# RapideUSB.net
KiCad netlist of a schematic drawn in EAGLE
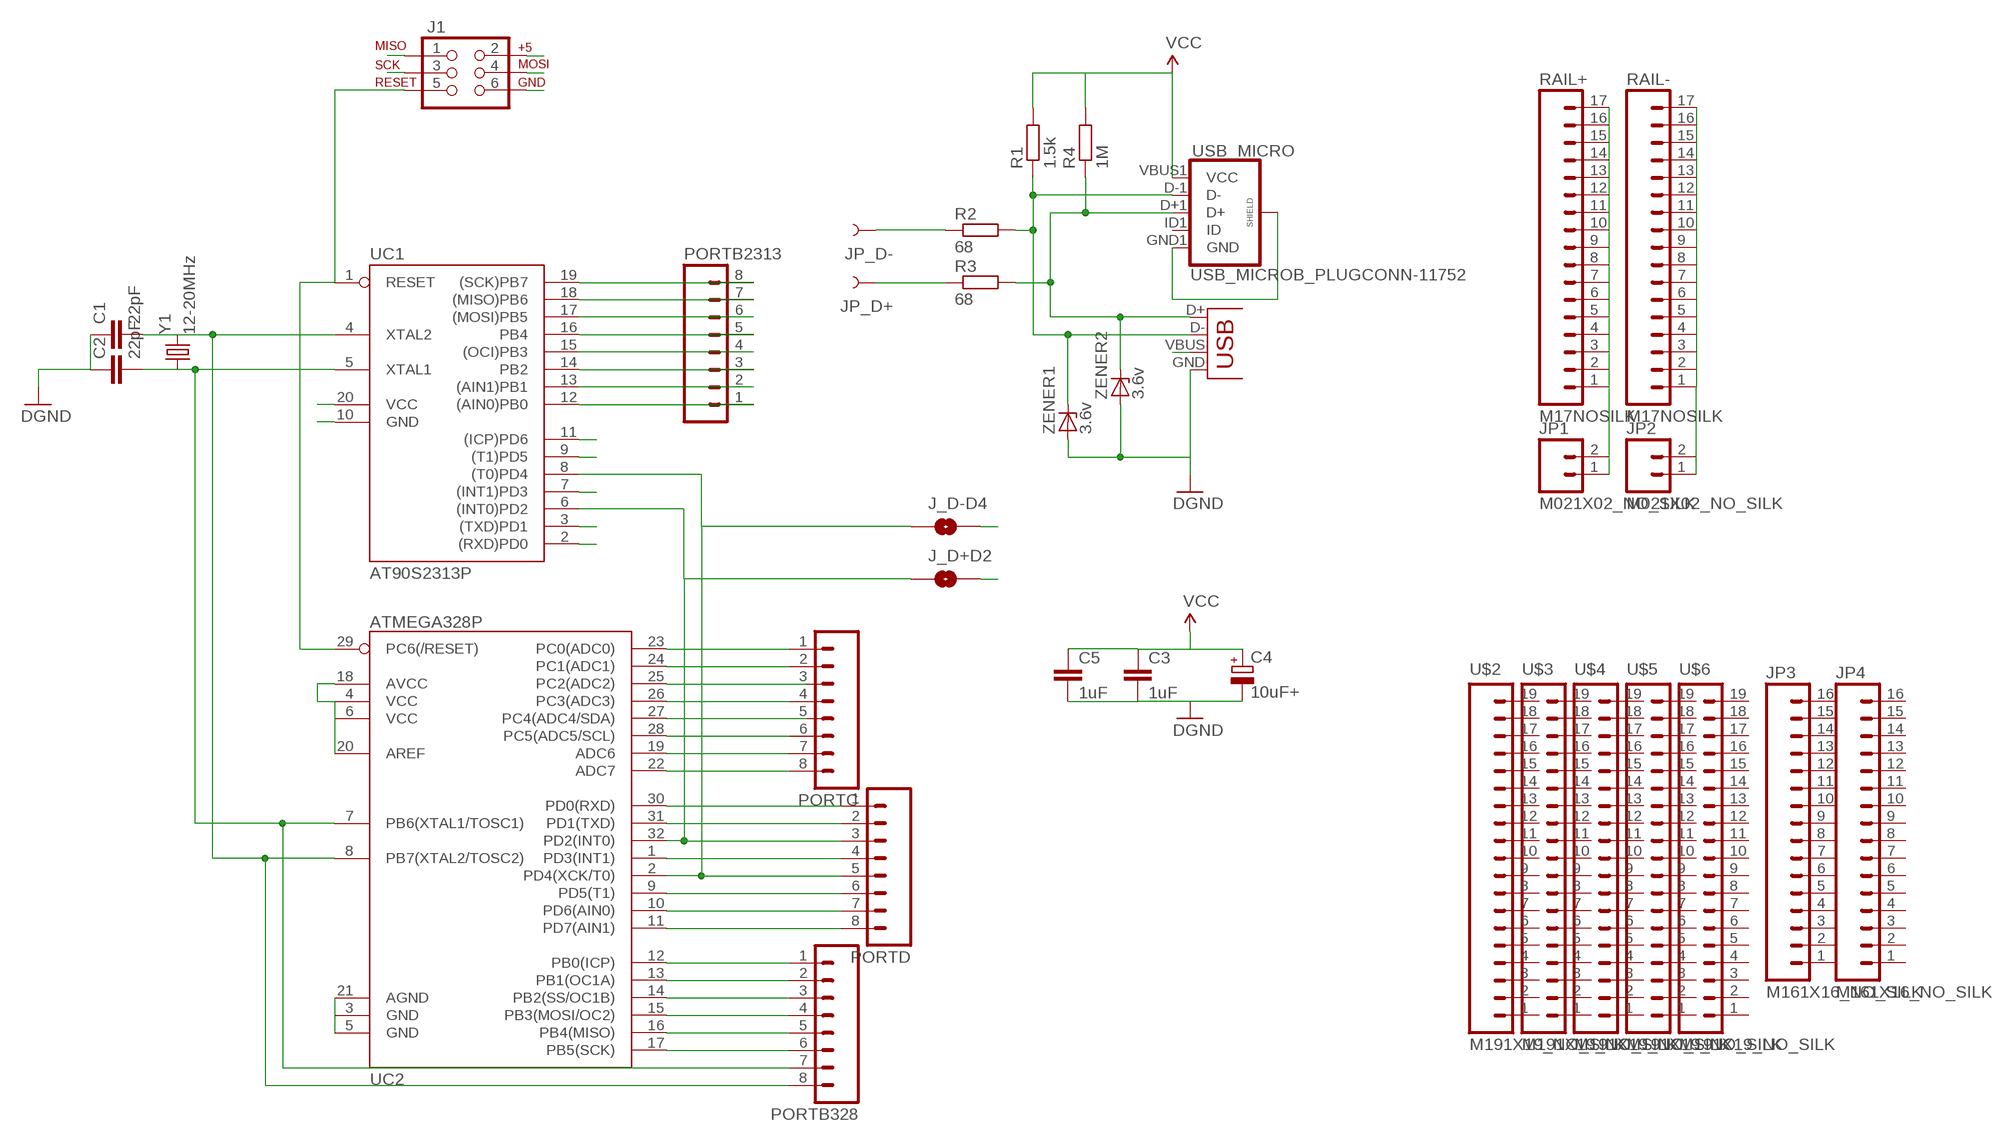
[diagram p0: schematic, sheet 1]

(export (version "E")
  (design (tool "Eeschema 10.0.6"))
  (components
    (comp (ref "C1")
      (value "22pF")
      (footprint "eagle-import:C025-024X044")
      (libsource (lib "eagle-import") (part "C-EU025-024X044"))
    )
    (comp (ref "C2")
      (value "22pF")
      (footprint "eagle-import:C025-024X044")
      (libsource (lib "eagle-import") (part "C-EU025-024X044"))
    )
    (comp (ref "C3")
      (value "1uF")
      (footprint "eagle-import:C025-024X044")
      (libsource (lib "eagle-import") (part "C-EU025-024X044"))
    )
    (comp (ref "C4")
      (value "10uF+")
      (footprint "eagle-import:E2-5")
      (libsource (lib "eagle-import") (part "CPOL-EUE2-5"))
    )
    (comp (ref "C5")
      (value "1uF")
      (footprint "eagle-import:C025-024X044")
      (libsource (lib "eagle-import") (part "C-EU025-024X044"))
    )
    (comp (ref "J1")
      (value "AVR_SPI_PRG_6PTH")
      (footprint "eagle-import:2X3")
      (libsource (lib "eagle-import") (part "AVR_SPI_PRG_6PTH"))
    )
    (comp (ref "JP1")
      (value "M021X02_NO_SILK")
      (footprint "eagle-import:1X02_NO_SILK")
      (libsource (lib "eagle-import") (part "M021X02_NO_SILK"))
    )
    (comp (ref "JP2")
      (value "M021X02_NO_SILK")
      (footprint "eagle-import:1X02_NO_SILK")
      (libsource (lib "eagle-import") (part "M021X02_NO_SILK"))
    )
    (comp (ref "JP3")
      (value "M161X16_NO_SILK")
      (footprint "eagle-import:1X16_NO_SILK")
      (libsource (lib "eagle-import") (part "M161X16_NO_SILK"))
    )
    (comp (ref "JP4")
      (value "M161X16_NO_SILK")
      (footprint "eagle-import:1X16_NO_SILK")
      (libsource (lib "eagle-import") (part "M161X16_NO_SILK"))
    )
    (comp (ref "JP_D+")
      (value "TEST-POINT3X5")
      (footprint "eagle-import:PAD.03X.05")
      (libsource (lib "eagle-import") (part "TEST-POINT3X5"))
    )
    (comp (ref "JP_D-")
      (value "TEST-POINT3X5")
      (footprint "eagle-import:PAD.03X.05")
      (libsource (lib "eagle-import") (part "TEST-POINT3X5"))
    )
    (comp (ref "J_D+D2")
      (value "JUMPER-PAD-2-NOYES_SILK")
      (footprint "eagle-import:PAD-JUMPER-2-NO_YES_SILK")
      (libsource (lib "eagle-import") (part "JUMPER-PAD-2-NOYES_SILK"))
    )
    (comp (ref "J_D-D4")
      (value "JUMPER-PAD-2-NOYES_SILK")
      (footprint "eagle-import:PAD-JUMPER-2-NO_YES_SILK")
      (libsource (lib "eagle-import") (part "JUMPER-PAD-2-NOYES_SILK"))
    )
    (comp (ref "PORTB328")
      (value "M081X08")
      (footprint "eagle-import:1X08")
      (libsource (lib "eagle-import") (part "M081X08"))
    )
    (comp (ref "PORTB2313")
      (value "M081X08")
      (footprint "eagle-import:1X08")
      (libsource (lib "eagle-import") (part "M081X08"))
    )
    (comp (ref "PORTC")
      (value "M081X08")
      (footprint "eagle-import:1X08")
      (libsource (lib "eagle-import") (part "M081X08"))
    )
    (comp (ref "PORTD")
      (value "M081X08")
      (footprint "eagle-import:1X08")
      (libsource (lib "eagle-import") (part "M081X08"))
    )
    (comp (ref "R1")
      (value "1.5k")
      (footprint "eagle-import:0204V")
      (libsource (lib "eagle-import") (part "R-EU_0204/2V"))
    )
    (comp (ref "R2")
      (value "68")
      (footprint "eagle-import:0204V")
      (libsource (lib "eagle-import") (part "R-EU_0204/2V"))
    )
    (comp (ref "R3")
      (value "68")
      (footprint "eagle-import:0204V")
      (libsource (lib "eagle-import") (part "R-EU_0204/2V"))
    )
    (comp (ref "R4")
      (value "1M")
      (footprint "eagle-import:0204V")
      (libsource (lib "eagle-import") (part "R-EU_0204/2V"))
    )
    (comp (ref "RAIL+")
      (value "M17NOSILK")
      (footprint "eagle-import:1X17_NO_SILK")
      (libsource (lib "eagle-import") (part "M17NOSILK"))
    )
    (comp (ref "RAIL-")
      (value "M17NOSILK")
      (footprint "eagle-import:1X17_NO_SILK")
      (libsource (lib "eagle-import") (part "M17NOSILK"))
    )
    (comp (ref "U$2")
      (value "M191X19_NO_SILK")
      (footprint "eagle-import:1X19_NO_SILK")
      (libsource (lib "eagle-import") (part "M191X19_NO_SILK"))
    )
    (comp (ref "U$3")
      (value "M191X19_NO_SILK")
      (footprint "eagle-import:1X19_NO_SILK")
      (libsource (lib "eagle-import") (part "M191X19_NO_SILK"))
    )
    (comp (ref "U$4")
      (value "M191X19_NO_SILK")
      (footprint "eagle-import:1X19_NO_SILK")
      (libsource (lib "eagle-import") (part "M191X19_NO_SILK"))
    )
    (comp (ref "U$5")
      (value "M191X19_NO_SILK")
      (footprint "eagle-import:1X19_NO_SILK")
      (libsource (lib "eagle-import") (part "M191X19_NO_SILK"))
    )
    (comp (ref "U$6")
      (value "M191X19_NO_SILK")
      (footprint "eagle-import:1X19_NO_SILK")
      (libsource (lib "eagle-import") (part "M191X19_NO_SILK"))
    )
    (comp (ref "UC1")
      (value "AT90S2313P")
      (footprint "eagle-import:DIL20")
      (libsource (lib "eagle-import") (part "AT90S2313P"))
    )
    (comp (ref "UC2")
      (value "ATMEGA328P")
      (footprint "eagle-import:TQFP32-08")
      (libsource (lib "eagle-import") (part "ATMEGA328_SMT"))
    )
    (comp (ref "USB_MICRO")
      (value "USB_MICROB_PLUGCONN-11752")
      (footprint "eagle-import:USB-B-MICRO-SMD_V03")
      (libsource (lib "eagle-import") (part "USB_MICROB_PLUGCONN-11752"))
    )
    (comp (ref "USB_MINI")
      (value "USBSMD")
      (footprint "eagle-import:USB-MINIB")
      (libsource (lib "eagle-import") (part "USBSMD"))
    )
    (comp (ref "Y1")
      (value "12-20MHz")
      (footprint "eagle-import:HC49U-V")
      (libsource (lib "eagle-import") (part "CRYSTALHC49UV"))
    )
    (comp (ref "ZENER1")
      (value "3.6v")
      (footprint "eagle-import:ZDIO-2.5")
      (libsource (lib "eagle-import") (part "ZENER-DIODEZD-2.5"))
    )
    (comp (ref "ZENER2")
      (value "3.6v")
      (footprint "eagle-import:ZDIO-2.5")
      (libsource (lib "eagle-import") (part "ZENER-DIODEZD-2.5"))
    )
  )
  (nets
    (net (code "1") (name "/D+") (class "Default")
      (node (ref "JP_D+") (pin "P$1") (pinfunction "1_P$1") (pintype "bidirectional"))
      (node (ref "J_D+D2") (pin "2") (pinfunction "2_2") (pintype "passive"))
      (node (ref "R3") (pin "1") (pinfunction "1_1") (pintype "passive"))
    )
    (net (code "2") (name "/D-") (class "Default")
      (node (ref "JP_D-") (pin "P$1") (pinfunction "1_P$1") (pintype "bidirectional"))
      (node (ref "J_D-D4") (pin "2") (pinfunction "2_2") (pintype "passive"))
      (node (ref "R2") (pin "1") (pinfunction "1_1") (pintype "passive"))
    )
    (net (code "3") (name "/D0") (class "Default")
      (node (ref "PORTD") (pin "1") (pinfunction "1_1") (pintype "passive"))
      (node (ref "UC1") (pin "2") (pinfunction "(RXD)PD0_2") (pintype "bidirectional"))
      (node (ref "UC2") (pin "30") (pinfunction "PD0(RXD)_30") (pintype "bidirectional"))
    )
    (net (code "4") (name "/D1") (class "Default")
      (node (ref "PORTD") (pin "2") (pinfunction "2_2") (pintype "passive"))
      (node (ref "UC1") (pin "3") (pinfunction "(TXD)PD1_3") (pintype "bidirectional"))
      (node (ref "UC2") (pin "31") (pinfunction "PD1(TXD)_31") (pintype "bidirectional"))
    )
    (net (code "5") (name "/D3") (class "Default")
      (node (ref "PORTD") (pin "4") (pinfunction "4_4") (pintype "passive"))
      (node (ref "UC1") (pin "7") (pinfunction "(INT1)PD3_7") (pintype "bidirectional"))
      (node (ref "UC2") (pin "1") (pinfunction "PD3(INT1)_1") (pintype "bidirectional"))
    )
    (net (code "6") (name "/D6") (class "Default")
      (node (ref "PORTD") (pin "7") (pinfunction "7_7") (pintype "passive"))
      (node (ref "UC1") (pin "11") (pinfunction "(ICP)PD6_11") (pintype "bidirectional"))
      (node (ref "UC2") (pin "10") (pinfunction "PD6(AIN0)_10") (pintype "bidirectional"))
    )
    (net (code "7") (name "/MISO") (class "Default")
      (node (ref "J1") (pin "1") (pinfunction "1_1") (pintype "passive"))
      (node (ref "PORTB2313") (pin "7") (pinfunction "7_7") (pintype "passive"))
      (node (ref "PORTB328") (pin "5") (pinfunction "5_5") (pintype "passive"))
      (node (ref "UC1") (pin "18") (pinfunction "(MISO)PB6_18") (pintype "bidirectional"))
      (node (ref "UC2") (pin "16") (pinfunction "PB4(MISO)_16") (pintype "bidirectional"))
    )
    (net (code "8") (name "/MOSI") (class "Default")
      (node (ref "J1") (pin "4") (pinfunction "4_4") (pintype "passive"))
      (node (ref "PORTB2313") (pin "6") (pinfunction "6_6") (pintype "passive"))
      (node (ref "PORTB328") (pin "4") (pinfunction "4_4") (pintype "passive"))
      (node (ref "UC1") (pin "17") (pinfunction "(MOSI)PB5_17") (pintype "bidirectional"))
      (node (ref "UC2") (pin "15") (pinfunction "PB3(MOSI/OC2)_15") (pintype "bidirectional"))
    )
    (net (code "9") (name "/SCK") (class "Default")
      (node (ref "J1") (pin "3") (pinfunction "3_3") (pintype "passive"))
      (node (ref "PORTB2313") (pin "8") (pinfunction "8_8") (pintype "passive"))
      (node (ref "PORTB328") (pin "6") (pinfunction "6_6") (pintype "passive"))
      (node (ref "UC1") (pin "19") (pinfunction "(SCK)PB7_19") (pintype "bidirectional"))
      (node (ref "UC2") (pin "17") (pinfunction "PB5(SCK)_17") (pintype "bidirectional"))
    )
    (net (code "10") (name "DGND") (class "Default")
      (node (ref "C1") (pin "1") (pinfunction "1_1") (pintype "passive"))
      (node (ref "C2") (pin "1") (pinfunction "1_1") (pintype "passive"))
      (node (ref "C3") (pin "2") (pinfunction "2_2") (pintype "passive"))
      (node (ref "C4") (pin "-") (pinfunction "-_-") (pintype "passive"))
      (node (ref "C5") (pin "2") (pinfunction "2_2") (pintype "passive"))
      (node (ref "J1") (pin "6") (pinfunction "6_6") (pintype "passive"))
      (node (ref "JP2") (pin "1") (pinfunction "1_1") (pintype "passive"))
      (node (ref "JP2") (pin "2") (pinfunction "2_2") (pintype "passive"))
      (node (ref "RAIL-") (pin "1") (pinfunction "1_1") (pintype "passive"))
      (node (ref "RAIL-") (pin "10") (pinfunction "10_10") (pintype "passive"))
      (node (ref "RAIL-") (pin "11") (pinfunction "11_11") (pintype "passive"))
      (node (ref "RAIL-") (pin "12") (pinfunction "12_12") (pintype "passive"))
      (node (ref "RAIL-") (pin "13") (pinfunction "13_13") (pintype "passive"))
      (node (ref "RAIL-") (pin "14") (pinfunction "14_14") (pintype "passive"))
      (node (ref "RAIL-") (pin "15") (pinfunction "15_15") (pintype "passive"))
      (node (ref "RAIL-") (pin "16") (pinfunction "16_16") (pintype "passive"))
      (node (ref "RAIL-") (pin "17") (pinfunction "17_17") (pintype "passive"))
      (node (ref "RAIL-") (pin "2") (pinfunction "2_2") (pintype "passive"))
      (node (ref "RAIL-") (pin "3") (pinfunction "3_3") (pintype "passive"))
      (node (ref "RAIL-") (pin "4") (pinfunction "4_4") (pintype "passive"))
      (node (ref "RAIL-") (pin "5") (pinfunction "5_5") (pintype "passive"))
      (node (ref "RAIL-") (pin "6") (pinfunction "6_6") (pintype "passive"))
      (node (ref "RAIL-") (pin "7") (pinfunction "7_7") (pintype "passive"))
      (node (ref "RAIL-") (pin "8") (pinfunction "8_8") (pintype "passive"))
      (node (ref "RAIL-") (pin "9") (pinfunction "9_9") (pintype "passive"))
      (node (ref "UC1") (pin "10") (pinfunction "GND_10") (pintype "power_in"))
      (node (ref "UC2") (pin "21") (pinfunction "AGND_21") (pintype "bidirectional"))
      (node (ref "UC2") (pin "3") (pinfunction "GND_3") (pintype "bidirectional"))
      (node (ref "UC2") (pin "5") (pinfunction "GND_5") (pintype "bidirectional"))
      (node (ref "USB_MICRO") (pin "GND1") (pinfunction "GND_GND1") (pintype "bidirectional"))
      (node (ref "USB_MICRO") (pin "SHIELD1") (pinfunction "SHIELD_SHIELD1") (pintype "bidirectional"))
      (node (ref "USB_MICRO") (pin "SHIELD2") (pinfunction "SHIELD_SHIELD2") (pintype "bidirectional"))
      (node (ref "USB_MICRO") (pin "SHIELD3") (pinfunction "SHIELD_SHIELD3") (pintype "bidirectional"))
      (node (ref "USB_MINI") (pin "GND") (pinfunction "GND_GND") (pintype "bidirectional"))
      (node (ref "ZENER1") (pin "A") (pinfunction "A_A") (pintype "passive"))
      (node (ref "ZENER2") (pin "A") (pinfunction "A_A") (pintype "passive"))
    )
    (net (code "11") (name "Net-(UC1-(AIN0)PB0)") (class "Default")
      (node (ref "PORTB2313") (pin "1") (pinfunction "1_1") (pintype "passive"))
      (node (ref "UC1") (pin "12") (pinfunction "(AIN0)PB0_12") (pintype "bidirectional"))
    )
    (net (code "12") (name "Net-(UC1-(AIN1)PB1)") (class "Default")
      (node (ref "PORTB2313") (pin "2") (pinfunction "2_2") (pintype "passive"))
      (node (ref "UC1") (pin "13") (pinfunction "(AIN1)PB1_13") (pintype "bidirectional"))
    )
    (net (code "13") (name "Net-(UC1-(INT0)PD2)") (class "Default")
      (node (ref "J_D+D2") (pin "1") (pinfunction "1_1") (pintype "passive"))
      (node (ref "PORTD") (pin "3") (pinfunction "3_3") (pintype "passive"))
      (node (ref "UC1") (pin "6") (pinfunction "(INT0)PD2_6") (pintype "bidirectional"))
      (node (ref "UC2") (pin "32") (pinfunction "PD2(INT0)_32") (pintype "bidirectional"))
    )
    (net (code "14") (name "Net-(UC1-(OCI)PB3)") (class "Default")
      (node (ref "PORTB2313") (pin "4") (pinfunction "4_4") (pintype "passive"))
      (node (ref "UC1") (pin "15") (pinfunction "(OCI)PB3_15") (pintype "bidirectional"))
    )
    (net (code "15") (name "Net-(UC1-(T0)PD4)") (class "Default")
      (node (ref "J_D-D4") (pin "1") (pinfunction "1_1") (pintype "passive"))
      (node (ref "PORTD") (pin "5") (pinfunction "5_5") (pintype "passive"))
      (node (ref "UC1") (pin "8") (pinfunction "(T0)PD4_8") (pintype "bidirectional"))
      (node (ref "UC2") (pin "2") (pinfunction "PD4(XCK/T0)_2") (pintype "bidirectional"))
    )
    (net (code "16") (name "Net-(UC1-PB2)") (class "Default")
      (node (ref "PORTB2313") (pin "3") (pinfunction "3_3") (pintype "passive"))
      (node (ref "UC1") (pin "14") (pinfunction "PB2_14") (pintype "bidirectional"))
    )
    (net (code "17") (name "Net-(UC1-PB4)") (class "Default")
      (node (ref "PORTB2313") (pin "5") (pinfunction "5_5") (pintype "passive"))
      (node (ref "UC1") (pin "16") (pinfunction "PB4_16") (pintype "bidirectional"))
    )
    (net (code "18") (name "Net-(UC1-RESET)") (class "Default")
      (node (ref "J1") (pin "5") (pinfunction "5_5") (pintype "passive"))
      (node (ref "UC1") (pin "1") (pinfunction "RESET_1") (pintype "bidirectional"))
      (node (ref "UC2") (pin "29") (pinfunction "PC6(/RESET)_29") (pintype "bidirectional"))
    )
    (net (code "19") (name "Net-(UC1-XTAL1)") (class "Default")
      (node (ref "C2") (pin "2") (pinfunction "2_2") (pintype "passive"))
      (node (ref "PORTB328") (pin "7") (pinfunction "7_7") (pintype "passive"))
      (node (ref "UC1") (pin "5") (pinfunction "XTAL1_5") (pintype "bidirectional"))
      (node (ref "UC2") (pin "7") (pinfunction "PB6(XTAL1/TOSC1)_7") (pintype "bidirectional"))
      (node (ref "Y1") (pin "1") (pinfunction "1_1") (pintype "passive"))
    )
    (net (code "20") (name "Net-(UC1-XTAL2)") (class "Default")
      (node (ref "C1") (pin "2") (pinfunction "2_2") (pintype "passive"))
      (node (ref "PORTB328") (pin "8") (pinfunction "8_8") (pintype "passive"))
      (node (ref "UC1") (pin "4") (pinfunction "XTAL2_4") (pintype "bidirectional"))
      (node (ref "UC2") (pin "8") (pinfunction "PB7(XTAL2/TOSC2)_8") (pintype "bidirectional"))
      (node (ref "Y1") (pin "2") (pinfunction "2_2") (pintype "passive"))
    )
    (net (code "21") (name "Net-(UC2-ADC6)") (class "Default")
      (node (ref "PORTC") (pin "7") (pinfunction "7_7") (pintype "passive"))
      (node (ref "UC2") (pin "19") (pinfunction "ADC6_19") (pintype "bidirectional"))
    )
    (net (code "22") (name "Net-(UC2-ADC7)") (class "Default")
      (node (ref "PORTC") (pin "8") (pinfunction "8_8") (pintype "passive"))
      (node (ref "UC2") (pin "22") (pinfunction "ADC7_22") (pintype "bidirectional"))
    )
    (net (code "23") (name "Net-(UC2-PB0(ICP))") (class "Default")
      (node (ref "PORTB328") (pin "1") (pinfunction "1_1") (pintype "passive"))
      (node (ref "UC2") (pin "12") (pinfunction "PB0(ICP)_12") (pintype "bidirectional"))
    )
    (net (code "24") (name "Net-(UC2-PB1(OC1A))") (class "Default")
      (node (ref "PORTB328") (pin "2") (pinfunction "2_2") (pintype "passive"))
      (node (ref "UC2") (pin "13") (pinfunction "PB1(OC1A)_13") (pintype "bidirectional"))
    )
    (net (code "25") (name "Net-(UC2-PB2(SS{slash}OC1B))") (class "Default")
      (node (ref "PORTB328") (pin "3") (pinfunction "3_3") (pintype "passive"))
      (node (ref "UC2") (pin "14") (pinfunction "PB2(SS/OC1B)_14") (pintype "bidirectional"))
    )
    (net (code "26") (name "Net-(UC2-PC0(ADC0))") (class "Default")
      (node (ref "PORTC") (pin "1") (pinfunction "1_1") (pintype "passive"))
      (node (ref "UC2") (pin "23") (pinfunction "PC0(ADC0)_23") (pintype "bidirectional"))
    )
    (net (code "27") (name "Net-(UC2-PC1(ADC1))") (class "Default")
      (node (ref "PORTC") (pin "2") (pinfunction "2_2") (pintype "passive"))
      (node (ref "UC2") (pin "24") (pinfunction "PC1(ADC1)_24") (pintype "bidirectional"))
    )
    (net (code "28") (name "Net-(UC2-PC3(ADC3))") (class "Default")
      (node (ref "PORTC") (pin "4") (pinfunction "4_4") (pintype "passive"))
      (node (ref "UC2") (pin "26") (pinfunction "PC3(ADC3)_26") (pintype "bidirectional"))
    )
    (net (code "29") (name "Net-(UC2-PC4(ADC4{slash}SDA))") (class "Default")
      (node (ref "PORTC") (pin "5") (pinfunction "5_5") (pintype "passive"))
      (node (ref "UC2") (pin "27") (pinfunction "PC4(ADC4/SDA)_27") (pintype "bidirectional"))
    )
    (net (code "30") (name "Net-(UC2-PC5(ADC5{slash}SCL))") (class "Default")
      (node (ref "PORTC") (pin "6") (pinfunction "6_6") (pintype "passive"))
      (node (ref "UC2") (pin "28") (pinfunction "PC5(ADC5/SCL)_28") (pintype "bidirectional"))
    )
    (net (code "31") (name "Net-(UC2-PD5(T1))") (class "Default")
      (node (ref "PORTD") (pin "6") (pinfunction "6_6") (pintype "passive"))
      (node (ref "UC2") (pin "9") (pinfunction "PD5(T1)_9") (pintype "bidirectional"))
    )
    (net (code "32") (name "Net-(UC2-PD7(AIN1))") (class "Default")
      (node (ref "PORTD") (pin "8") (pinfunction "8_8") (pintype "passive"))
      (node (ref "UC2") (pin "11") (pinfunction "PD7(AIN1)_11") (pintype "bidirectional"))
    )
    (net (code "33") (name "Net-(USB_MICRO-D+)") (class "Default")
      (node (ref "R3") (pin "2") (pinfunction "2_2") (pintype "passive"))
      (node (ref "R4") (pin "1") (pinfunction "1_1") (pintype "passive"))
      (node (ref "USB_MICRO") (pin "D+1") (pinfunction "D+_D+1") (pintype "bidirectional"))
      (node (ref "USB_MINI") (pin "D+") (pinfunction "D+_D+") (pintype "bidirectional"))
      (node (ref "ZENER2") (pin "C") (pinfunction "C_C") (pintype "passive"))
    )
    (net (code "34") (name "Net-(USB_MICRO-D-)") (class "Default")
      (node (ref "R1") (pin "1") (pinfunction "1_1") (pintype "passive"))
      (node (ref "R2") (pin "2") (pinfunction "2_2") (pintype "passive"))
      (node (ref "USB_MICRO") (pin "D-1") (pinfunction "D-_D-1") (pintype "bidirectional"))
      (node (ref "USB_MINI") (pin "D-") (pinfunction "D-_D-") (pintype "bidirectional"))
      (node (ref "ZENER1") (pin "C") (pinfunction "C_C") (pintype "passive"))
    )
    (net (code "35") (name "VCC") (class "Default")
      (node (ref "C3") (pin "1") (pinfunction "1_1") (pintype "passive"))
      (node (ref "C4") (pin "+") (pinfunction "+_+") (pintype "passive"))
      (node (ref "C5") (pin "1") (pinfunction "1_1") (pintype "passive"))
      (node (ref "J1") (pin "2") (pinfunction "2_2") (pintype "passive"))
      (node (ref "JP1") (pin "1") (pinfunction "1_1") (pintype "passive"))
      (node (ref "JP1") (pin "2") (pinfunction "2_2") (pintype "passive"))
      (node (ref "R1") (pin "2") (pinfunction "2_2") (pintype "passive"))
      (node (ref "R4") (pin "2") (pinfunction "2_2") (pintype "passive"))
      (node (ref "RAIL+") (pin "1") (pinfunction "1_1") (pintype "passive"))
      (node (ref "RAIL+") (pin "10") (pinfunction "10_10") (pintype "passive"))
      (node (ref "RAIL+") (pin "11") (pinfunction "11_11") (pintype "passive"))
      (node (ref "RAIL+") (pin "12") (pinfunction "12_12") (pintype "passive"))
      (node (ref "RAIL+") (pin "13") (pinfunction "13_13") (pintype "passive"))
      (node (ref "RAIL+") (pin "14") (pinfunction "14_14") (pintype "passive"))
      (node (ref "RAIL+") (pin "15") (pinfunction "15_15") (pintype "passive"))
      (node (ref "RAIL+") (pin "16") (pinfunction "16_16") (pintype "passive"))
      (node (ref "RAIL+") (pin "17") (pinfunction "17_17") (pintype "passive"))
      (node (ref "RAIL+") (pin "2") (pinfunction "2_2") (pintype "passive"))
      (node (ref "RAIL+") (pin "3") (pinfunction "3_3") (pintype "passive"))
      (node (ref "RAIL+") (pin "4") (pinfunction "4_4") (pintype "passive"))
      (node (ref "RAIL+") (pin "5") (pinfunction "5_5") (pintype "passive"))
      (node (ref "RAIL+") (pin "6") (pinfunction "6_6") (pintype "passive"))
      (node (ref "RAIL+") (pin "7") (pinfunction "7_7") (pintype "passive"))
      (node (ref "RAIL+") (pin "8") (pinfunction "8_8") (pintype "passive"))
      (node (ref "RAIL+") (pin "9") (pinfunction "9_9") (pintype "passive"))
      (node (ref "UC1") (pin "20") (pinfunction "VCC_20") (pintype "power_in"))
      (node (ref "UC2") (pin "18") (pinfunction "AVCC_18") (pintype "bidirectional"))
      (node (ref "UC2") (pin "20") (pinfunction "AREF_20") (pintype "bidirectional"))
      (node (ref "UC2") (pin "4") (pinfunction "VCC_4") (pintype "bidirectional"))
      (node (ref "UC2") (pin "6") (pinfunction "VCC_6") (pintype "bidirectional"))
      (node (ref "USB_MICRO") (pin "VBUS1") (pinfunction "VCC_VBUS1") (pintype "bidirectional"))
      (node (ref "USB_MINI") (pin "VBUS") (pinfunction "VBUS_VBUS") (pintype "bidirectional"))
    )
    (net (code "36") (name "unconnected-(JP3-Pad1)") (class "Default")
      (node (ref "JP3") (pin "1") (pinfunction "1_1") (pintype "passive"))
    )
    (net (code "37") (name "unconnected-(JP3-Pad2)") (class "Default")
      (node (ref "JP3") (pin "2") (pinfunction "2_2") (pintype "passive"))
    )
    (net (code "38") (name "unconnected-(JP3-Pad3)") (class "Default")
      (node (ref "JP3") (pin "3") (pinfunction "3_3") (pintype "passive"))
    )
    (net (code "39") (name "unconnected-(JP3-Pad4)") (class "Default")
      (node (ref "JP3") (pin "4") (pinfunction "4_4") (pintype "passive"))
    )
    (net (code "40") (name "unconnected-(JP3-Pad5)") (class "Default")
      (node (ref "JP3") (pin "5") (pinfunction "5_5") (pintype "passive"))
    )
    (net (code "41") (name "unconnected-(JP3-Pad6)") (class "Default")
      (node (ref "JP3") (pin "6") (pinfunction "6_6") (pintype "passive"))
    )
    (net (code "42") (name "unconnected-(JP3-Pad7)") (class "Default")
      (node (ref "JP3") (pin "7") (pinfunction "7_7") (pintype "passive"))
    )
    (net (code "43") (name "unconnected-(JP3-Pad8)") (class "Default")
      (node (ref "JP3") (pin "8") (pinfunction "8_8") (pintype "passive"))
    )
    (net (code "44") (name "unconnected-(JP3-Pad9)") (class "Default")
      (node (ref "JP3") (pin "9") (pinfunction "9_9") (pintype "passive"))
    )
    (net (code "45") (name "unconnected-(JP3-Pad10)") (class "Default")
      (node (ref "JP3") (pin "10") (pinfunction "10_10") (pintype "passive"))
    )
    (net (code "46") (name "unconnected-(JP3-Pad11)") (class "Default")
      (node (ref "JP3") (pin "11") (pinfunction "11_11") (pintype "passive"))
    )
    (net (code "47") (name "unconnected-(JP3-Pad12)") (class "Default")
      (node (ref "JP3") (pin "12") (pinfunction "12_12") (pintype "passive"))
    )
    (net (code "48") (name "unconnected-(JP3-Pad13)") (class "Default")
      (node (ref "JP3") (pin "13") (pinfunction "13_13") (pintype "passive"))
    )
    (net (code "49") (name "unconnected-(JP3-Pad14)") (class "Default")
      (node (ref "JP3") (pin "14") (pinfunction "14_14") (pintype "passive"))
    )
    (net (code "50") (name "unconnected-(JP3-Pad15)") (class "Default")
      (node (ref "JP3") (pin "15") (pinfunction "15_15") (pintype "passive"))
    )
    (net (code "51") (name "unconnected-(JP3-Pad16)") (class "Default")
      (node (ref "JP3") (pin "16") (pinfunction "16_16") (pintype "passive"))
    )
    (net (code "52") (name "unconnected-(JP4-Pad1)") (class "Default")
      (node (ref "JP4") (pin "1") (pinfunction "1_1") (pintype "passive"))
    )
    (net (code "53") (name "unconnected-(JP4-Pad2)") (class "Default")
      (node (ref "JP4") (pin "2") (pinfunction "2_2") (pintype "passive"))
    )
    (net (code "54") (name "unconnected-(JP4-Pad3)") (class "Default")
      (node (ref "JP4") (pin "3") (pinfunction "3_3") (pintype "passive"))
    )
    (net (code "55") (name "unconnected-(JP4-Pad4)") (class "Default")
      (node (ref "JP4") (pin "4") (pinfunction "4_4") (pintype "passive"))
    )
    (net (code "56") (name "unconnected-(JP4-Pad5)") (class "Default")
      (node (ref "JP4") (pin "5") (pinfunction "5_5") (pintype "passive"))
    )
    (net (code "57") (name "unconnected-(JP4-Pad6)") (class "Default")
      (node (ref "JP4") (pin "6") (pinfunction "6_6") (pintype "passive"))
    )
    (net (code "58") (name "unconnected-(JP4-Pad7)") (class "Default")
      (node (ref "JP4") (pin "7") (pinfunction "7_7") (pintype "passive"))
    )
    (net (code "59") (name "unconnected-(JP4-Pad8)") (class "Default")
      (node (ref "JP4") (pin "8") (pinfunction "8_8") (pintype "passive"))
    )
    (net (code "60") (name "unconnected-(JP4-Pad9)") (class "Default")
      (node (ref "JP4") (pin "9") (pinfunction "9_9") (pintype "passive"))
    )
    (net (code "61") (name "unconnected-(JP4-Pad10)") (class "Default")
      (node (ref "JP4") (pin "10") (pinfunction "10_10") (pintype "passive"))
    )
    (net (code "62") (name "unconnected-(JP4-Pad11)") (class "Default")
      (node (ref "JP4") (pin "11") (pinfunction "11_11") (pintype "passive"))
    )
    (net (code "63") (name "unconnected-(JP4-Pad12)") (class "Default")
      (node (ref "JP4") (pin "12") (pinfunction "12_12") (pintype "passive"))
    )
    (net (code "64") (name "unconnected-(JP4-Pad13)") (class "Default")
      (node (ref "JP4") (pin "13") (pinfunction "13_13") (pintype "passive"))
    )
    (net (code "65") (name "unconnected-(JP4-Pad14)") (class "Default")
      (node (ref "JP4") (pin "14") (pinfunction "14_14") (pintype "passive"))
    )
    (net (code "66") (name "unconnected-(JP4-Pad15)") (class "Default")
      (node (ref "JP4") (pin "15") (pinfunction "15_15") (pintype "passive"))
    )
    (net (code "67") (name "unconnected-(JP4-Pad16)") (class "Default")
      (node (ref "JP4") (pin "16") (pinfunction "16_16") (pintype "passive"))
    )
    (net (code "68") (name "unconnected-(PORTC-Pad3)") (class "Default")
      (node (ref "PORTC") (pin "3") (pinfunction "3_3") (pintype "passive"))
    )
    (net (code "69") (name "unconnected-(U$2-Pad1)") (class "Default")
      (node (ref "U$2") (pin "1") (pinfunction "1_1") (pintype "passive"))
    )
    (net (code "70") (name "unconnected-(U$2-Pad2)") (class "Default")
      (node (ref "U$2") (pin "2") (pinfunction "2_2") (pintype "passive"))
    )
    (net (code "71") (name "unconnected-(U$2-Pad3)") (class "Default")
      (node (ref "U$2") (pin "3") (pinfunction "3_3") (pintype "passive"))
    )
    (net (code "72") (name "unconnected-(U$2-Pad4)") (class "Default")
      (node (ref "U$2") (pin "4") (pinfunction "4_4") (pintype "passive"))
    )
    (net (code "73") (name "unconnected-(U$2-Pad5)") (class "Default")
      (node (ref "U$2") (pin "5") (pinfunction "5_5") (pintype "passive"))
    )
    (net (code "74") (name "unconnected-(U$2-Pad6)") (class "Default")
      (node (ref "U$2") (pin "6") (pinfunction "6_6") (pintype "passive"))
    )
    (net (code "75") (name "unconnected-(U$2-Pad7)") (class "Default")
      (node (ref "U$2") (pin "7") (pinfunction "7_7") (pintype "passive"))
    )
    (net (code "76") (name "unconnected-(U$2-Pad8)") (class "Default")
      (node (ref "U$2") (pin "8") (pinfunction "8_8") (pintype "passive"))
    )
    (net (code "77") (name "unconnected-(U$2-Pad9)") (class "Default")
      (node (ref "U$2") (pin "9") (pinfunction "9_9") (pintype "passive"))
    )
    (net (code "78") (name "unconnected-(U$2-Pad10)") (class "Default")
      (node (ref "U$2") (pin "10") (pinfunction "10_10") (pintype "passive"))
    )
    (net (code "79") (name "unconnected-(U$2-Pad11)") (class "Default")
      (node (ref "U$2") (pin "11") (pinfunction "11_11") (pintype "passive"))
    )
    (net (code "80") (name "unconnected-(U$2-Pad12)") (class "Default")
      (node (ref "U$2") (pin "12") (pinfunction "12_12") (pintype "passive"))
    )
    (net (code "81") (name "unconnected-(U$2-Pad13)") (class "Default")
      (node (ref "U$2") (pin "13") (pinfunction "13_13") (pintype "passive"))
    )
    (net (code "82") (name "unconnected-(U$2-Pad14)") (class "Default")
      (node (ref "U$2") (pin "14") (pinfunction "14_14") (pintype "passive"))
    )
    (net (code "83") (name "unconnected-(U$2-Pad15)") (class "Default")
      (node (ref "U$2") (pin "15") (pinfunction "15_15") (pintype "passive"))
    )
    (net (code "84") (name "unconnected-(U$2-Pad16)") (class "Default")
      (node (ref "U$2") (pin "16") (pinfunction "16_16") (pintype "passive"))
    )
    (net (code "85") (name "unconnected-(U$2-Pad17)") (class "Default")
      (node (ref "U$2") (pin "17") (pinfunction "17_17") (pintype "passive"))
    )
    (net (code "86") (name "unconnected-(U$2-Pad18)") (class "Default")
      (node (ref "U$2") (pin "18") (pinfunction "18_18") (pintype "passive"))
    )
    (net (code "87") (name "unconnected-(U$2-Pad19)") (class "Default")
      (node (ref "U$2") (pin "19") (pinfunction "19_19") (pintype "passive"))
    )
    (net (code "88") (name "unconnected-(U$3-Pad1)") (class "Default")
      (node (ref "U$3") (pin "1") (pinfunction "1_1") (pintype "passive"))
    )
    (net (code "89") (name "unconnected-(U$3-Pad2)") (class "Default")
      (node (ref "U$3") (pin "2") (pinfunction "2_2") (pintype "passive"))
    )
    (net (code "90") (name "unconnected-(U$3-Pad3)") (class "Default")
      (node (ref "U$3") (pin "3") (pinfunction "3_3") (pintype "passive"))
    )
    (net (code "91") (name "unconnected-(U$3-Pad4)") (class "Default")
      (node (ref "U$3") (pin "4") (pinfunction "4_4") (pintype "passive"))
    )
    (net (code "92") (name "unconnected-(U$3-Pad5)") (class "Default")
      (node (ref "U$3") (pin "5") (pinfunction "5_5") (pintype "passive"))
    )
    (net (code "93") (name "unconnected-(U$3-Pad6)") (class "Default")
      (node (ref "U$3") (pin "6") (pinfunction "6_6") (pintype "passive"))
    )
    (net (code "94") (name "unconnected-(U$3-Pad7)") (class "Default")
      (node (ref "U$3") (pin "7") (pinfunction "7_7") (pintype "passive"))
    )
    (net (code "95") (name "unconnected-(U$3-Pad8)") (class "Default")
      (node (ref "U$3") (pin "8") (pinfunction "8_8") (pintype "passive"))
    )
    (net (code "96") (name "unconnected-(U$3-Pad9)") (class "Default")
      (node (ref "U$3") (pin "9") (pinfunction "9_9") (pintype "passive"))
    )
    (net (code "97") (name "unconnected-(U$3-Pad10)") (class "Default")
      (node (ref "U$3") (pin "10") (pinfunction "10_10") (pintype "passive"))
    )
    (net (code "98") (name "unconnected-(U$3-Pad11)") (class "Default")
      (node (ref "U$3") (pin "11") (pinfunction "11_11") (pintype "passive"))
    )
    (net (code "99") (name "unconnected-(U$3-Pad12)") (class "Default")
      (node (ref "U$3") (pin "12") (pinfunction "12_12") (pintype "passive"))
    )
    (net (code "100") (name "unconnected-(U$3-Pad13)") (class "Default")
      (node (ref "U$3") (pin "13") (pinfunction "13_13") (pintype "passive"))
    )
    (net (code "101") (name "unconnected-(U$3-Pad14)") (class "Default")
      (node (ref "U$3") (pin "14") (pinfunction "14_14") (pintype "passive"))
    )
    (net (code "102") (name "unconnected-(U$3-Pad15)") (class "Default")
      (node (ref "U$3") (pin "15") (pinfunction "15_15") (pintype "passive"))
    )
    (net (code "103") (name "unconnected-(U$3-Pad16)") (class "Default")
      (node (ref "U$3") (pin "16") (pinfunction "16_16") (pintype "passive"))
    )
    (net (code "104") (name "unconnected-(U$3-Pad17)") (class "Default")
      (node (ref "U$3") (pin "17") (pinfunction "17_17") (pintype "passive"))
    )
    (net (code "105") (name "unconnected-(U$3-Pad18)") (class "Default")
      (node (ref "U$3") (pin "18") (pinfunction "18_18") (pintype "passive"))
    )
    (net (code "106") (name "unconnected-(U$3-Pad19)") (class "Default")
      (node (ref "U$3") (pin "19") (pinfunction "19_19") (pintype "passive"))
    )
    (net (code "107") (name "unconnected-(U$4-Pad1)") (class "Default")
      (node (ref "U$4") (pin "1") (pinfunction "1_1") (pintype "passive"))
    )
    (net (code "108") (name "unconnected-(U$4-Pad2)") (class "Default")
      (node (ref "U$4") (pin "2") (pinfunction "2_2") (pintype "passive"))
    )
    (net (code "109") (name "unconnected-(U$4-Pad3)") (class "Default")
      (node (ref "U$4") (pin "3") (pinfunction "3_3") (pintype "passive"))
    )
    (net (code "110") (name "unconnected-(U$4-Pad4)") (class "Default")
      (node (ref "U$4") (pin "4") (pinfunction "4_4") (pintype "passive"))
    )
    (net (code "111") (name "unconnected-(U$4-Pad5)") (class "Default")
      (node (ref "U$4") (pin "5") (pinfunction "5_5") (pintype "passive"))
    )
    (net (code "112") (name "unconnected-(U$4-Pad6)") (class "Default")
      (node (ref "U$4") (pin "6") (pinfunction "6_6") (pintype "passive"))
    )
    (net (code "113") (name "unconnected-(U$4-Pad7)") (class "Default")
      (node (ref "U$4") (pin "7") (pinfunction "7_7") (pintype "passive"))
    )
    (net (code "114") (name "unconnected-(U$4-Pad8)") (class "Default")
      (node (ref "U$4") (pin "8") (pinfunction "8_8") (pintype "passive"))
    )
    (net (code "115") (name "unconnected-(U$4-Pad9)") (class "Default")
      (node (ref "U$4") (pin "9") (pinfunction "9_9") (pintype "passive"))
    )
    (net (code "116") (name "unconnected-(U$4-Pad10)") (class "Default")
      (node (ref "U$4") (pin "10") (pinfunction "10_10") (pintype "passive"))
    )
    (net (code "117") (name "unconnected-(U$4-Pad11)") (class "Default")
      (node (ref "U$4") (pin "11") (pinfunction "11_11") (pintype "passive"))
    )
    (net (code "118") (name "unconnected-(U$4-Pad12)") (class "Default")
      (node (ref "U$4") (pin "12") (pinfunction "12_12") (pintype "passive"))
    )
    (net (code "119") (name "unconnected-(U$4-Pad13)") (class "Default")
      (node (ref "U$4") (pin "13") (pinfunction "13_13") (pintype "passive"))
    )
    (net (code "120") (name "unconnected-(U$4-Pad14)") (class "Default")
      (node (ref "U$4") (pin "14") (pinfunction "14_14") (pintype "passive"))
    )
    (net (code "121") (name "unconnected-(U$4-Pad15)") (class "Default")
      (node (ref "U$4") (pin "15") (pinfunction "15_15") (pintype "passive"))
    )
    (net (code "122") (name "unconnected-(U$4-Pad16)") (class "Default")
      (node (ref "U$4") (pin "16") (pinfunction "16_16") (pintype "passive"))
    )
    (net (code "123") (name "unconnected-(U$4-Pad17)") (class "Default")
      (node (ref "U$4") (pin "17") (pinfunction "17_17") (pintype "passive"))
    )
    (net (code "124") (name "unconnected-(U$4-Pad18)") (class "Default")
      (node (ref "U$4") (pin "18") (pinfunction "18_18") (pintype "passive"))
    )
    (net (code "125") (name "unconnected-(U$4-Pad19)") (class "Default")
      (node (ref "U$4") (pin "19") (pinfunction "19_19") (pintype "passive"))
    )
    (net (code "126") (name "unconnected-(U$5-Pad1)") (class "Default")
      (node (ref "U$5") (pin "1") (pinfunction "1_1") (pintype "passive"))
    )
    (net (code "127") (name "unconnected-(U$5-Pad2)") (class "Default")
      (node (ref "U$5") (pin "2") (pinfunction "2_2") (pintype "passive"))
    )
    (net (code "128") (name "unconnected-(U$5-Pad3)") (class "Default")
      (node (ref "U$5") (pin "3") (pinfunction "3_3") (pintype "passive"))
    )
    (net (code "129") (name "unconnected-(U$5-Pad4)") (class "Default")
      (node (ref "U$5") (pin "4") (pinfunction "4_4") (pintype "passive"))
    )
    (net (code "130") (name "unconnected-(U$5-Pad5)") (class "Default")
      (node (ref "U$5") (pin "5") (pinfunction "5_5") (pintype "passive"))
    )
    (net (code "131") (name "unconnected-(U$5-Pad6)") (class "Default")
      (node (ref "U$5") (pin "6") (pinfunction "6_6") (pintype "passive"))
    )
    (net (code "132") (name "unconnected-(U$5-Pad7)") (class "Default")
      (node (ref "U$5") (pin "7") (pinfunction "7_7") (pintype "passive"))
    )
    (net (code "133") (name "unconnected-(U$5-Pad8)") (class "Default")
      (node (ref "U$5") (pin "8") (pinfunction "8_8") (pintype "passive"))
    )
    (net (code "134") (name "unconnected-(U$5-Pad9)") (class "Default")
      (node (ref "U$5") (pin "9") (pinfunction "9_9") (pintype "passive"))
    )
    (net (code "135") (name "unconnected-(U$5-Pad10)") (class "Default")
      (node (ref "U$5") (pin "10") (pinfunction "10_10") (pintype "passive"))
    )
    (net (code "136") (name "unconnected-(U$5-Pad11)") (class "Default")
      (node (ref "U$5") (pin "11") (pinfunction "11_11") (pintype "passive"))
    )
    (net (code "137") (name "unconnected-(U$5-Pad12)") (class "Default")
      (node (ref "U$5") (pin "12") (pinfunction "12_12") (pintype "passive"))
    )
    (net (code "138") (name "unconnected-(U$5-Pad13)") (class "Default")
      (node (ref "U$5") (pin "13") (pinfunction "13_13") (pintype "passive"))
    )
    (net (code "139") (name "unconnected-(U$5-Pad14)") (class "Default")
      (node (ref "U$5") (pin "14") (pinfunction "14_14") (pintype "passive"))
    )
    (net (code "140") (name "unconnected-(U$5-Pad15)") (class "Default")
      (node (ref "U$5") (pin "15") (pinfunction "15_15") (pintype "passive"))
    )
    (net (code "141") (name "unconnected-(U$5-Pad16)") (class "Default")
      (node (ref "U$5") (pin "16") (pinfunction "16_16") (pintype "passive"))
    )
    (net (code "142") (name "unconnected-(U$5-Pad17)") (class "Default")
      (node (ref "U$5") (pin "17") (pinfunction "17_17") (pintype "passive"))
    )
    (net (code "143") (name "unconnected-(U$5-Pad18)") (class "Default")
      (node (ref "U$5") (pin "18") (pinfunction "18_18") (pintype "passive"))
    )
    (net (code "144") (name "unconnected-(U$5-Pad19)") (class "Default")
      (node (ref "U$5") (pin "19") (pinfunction "19_19") (pintype "passive"))
    )
    (net (code "145") (name "unconnected-(U$6-Pad1)") (class "Default")
      (node (ref "U$6") (pin "1") (pinfunction "1_1") (pintype "passive"))
    )
    (net (code "146") (name "unconnected-(U$6-Pad2)") (class "Default")
      (node (ref "U$6") (pin "2") (pinfunction "2_2") (pintype "passive"))
    )
    (net (code "147") (name "unconnected-(U$6-Pad3)") (class "Default")
      (node (ref "U$6") (pin "3") (pinfunction "3_3") (pintype "passive"))
    )
    (net (code "148") (name "unconnected-(U$6-Pad4)") (class "Default")
      (node (ref "U$6") (pin "4") (pinfunction "4_4") (pintype "passive"))
    )
    (net (code "149") (name "unconnected-(U$6-Pad5)") (class "Default")
      (node (ref "U$6") (pin "5") (pinfunction "5_5") (pintype "passive"))
    )
    (net (code "150") (name "unconnected-(U$6-Pad6)") (class "Default")
      (node (ref "U$6") (pin "6") (pinfunction "6_6") (pintype "passive"))
    )
    (net (code "151") (name "unconnected-(U$6-Pad7)") (class "Default")
      (node (ref "U$6") (pin "7") (pinfunction "7_7") (pintype "passive"))
    )
    (net (code "152") (name "unconnected-(U$6-Pad8)") (class "Default")
      (node (ref "U$6") (pin "8") (pinfunction "8_8") (pintype "passive"))
    )
    (net (code "153") (name "unconnected-(U$6-Pad9)") (class "Default")
      (node (ref "U$6") (pin "9") (pinfunction "9_9") (pintype "passive"))
    )
    (net (code "154") (name "unconnected-(U$6-Pad10)") (class "Default")
      (node (ref "U$6") (pin "10") (pinfunction "10_10") (pintype "passive"))
    )
    (net (code "155") (name "unconnected-(U$6-Pad11)") (class "Default")
      (node (ref "U$6") (pin "11") (pinfunction "11_11") (pintype "passive"))
    )
    (net (code "156") (name "unconnected-(U$6-Pad12)") (class "Default")
      (node (ref "U$6") (pin "12") (pinfunction "12_12") (pintype "passive"))
    )
    (net (code "157") (name "unconnected-(U$6-Pad13)") (class "Default")
      (node (ref "U$6") (pin "13") (pinfunction "13_13") (pintype "passive"))
    )
    (net (code "158") (name "unconnected-(U$6-Pad14)") (class "Default")
      (node (ref "U$6") (pin "14") (pinfunction "14_14") (pintype "passive"))
    )
    (net (code "159") (name "unconnected-(U$6-Pad15)") (class "Default")
      (node (ref "U$6") (pin "15") (pinfunction "15_15") (pintype "passive"))
    )
    (net (code "160") (name "unconnected-(U$6-Pad16)") (class "Default")
      (node (ref "U$6") (pin "16") (pinfunction "16_16") (pintype "passive"))
    )
    (net (code "161") (name "unconnected-(U$6-Pad17)") (class "Default")
      (node (ref "U$6") (pin "17") (pinfunction "17_17") (pintype "passive"))
    )
    (net (code "162") (name "unconnected-(U$6-Pad18)") (class "Default")
      (node (ref "U$6") (pin "18") (pinfunction "18_18") (pintype "passive"))
    )
    (net (code "163") (name "unconnected-(U$6-Pad19)") (class "Default")
      (node (ref "U$6") (pin "19") (pinfunction "19_19") (pintype "passive"))
    )
    (net (code "164") (name "unconnected-(UC1-(T1)PD5-Pad9)") (class "Default")
      (node (ref "UC1") (pin "9") (pinfunction "(T1)PD5_9") (pintype "bidirectional"))
    )
    (net (code "165") (name "unconnected-(UC2-PC2(ADC2)-Pad25)") (class "Default")
      (node (ref "UC2") (pin "25") (pinfunction "PC2(ADC2)_25") (pintype "bidirectional"))
    )
    (net (code "166") (name "unconnected-(USB_MICRO-ID-PadID1)") (class "Default")
      (node (ref "USB_MICRO") (pin "ID1") (pinfunction "ID_ID1") (pintype "bidirectional"))
    )
  )
)
